# Sheet1.net
KiCad netlist of a schematic drawn in Altium Designer
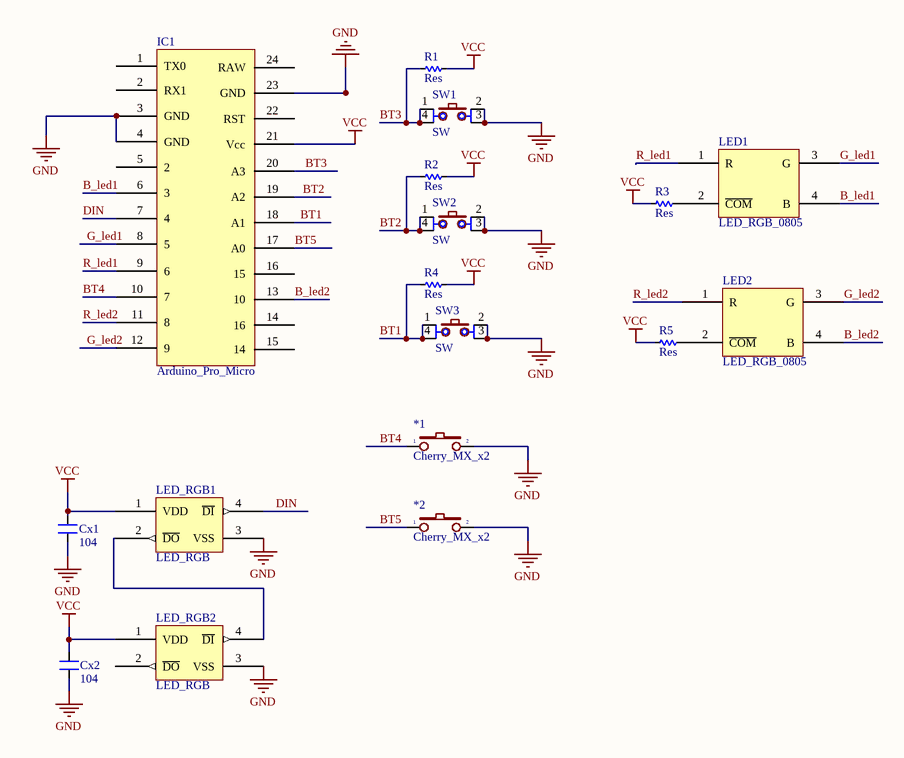
[diagram p0: Sheet1.SchDoc]

(export (version "E")
  (design (tool "Eeschema 10.0.6"))
  (components
    (comp (ref "*1")
      (value "Cherry_MX_x2")
      (footprint "Cherry_Mx_2")
      (libsource (lib "LIBRARY") (part "Cherry_MX_x2"))
    )
    (comp (ref "*2")
      (value "Cherry_MX_x2")
      (footprint "Cherry_Mx_2")
      (libsource (lib "LIBRARY") (part "Cherry_MX_x2"))
    )
    (comp (ref "Cx1") (value "104") (footprint "CN-SMD-0805") (libsource (lib "LIBRARY") (part "CN")))
    (comp (ref "Cx2") (value "104") (footprint "CN-SMD-0805") (libsource (lib "LIBRARY") (part "CN")))
    (comp (ref "IC1")
      (value "Arduino_Pro_Micro")
      (footprint "PCBComponent_1")
      (libsource (lib "LIBRARY") (part "Arduino_Pro_Micro"))
    )
    (comp (ref "LED1")
      (value "LED_RGB_0805")
      (footprint "PCBComponent_1")
      (libsource (lib "LED_RGB_0805") (part "LED_RGB_0805"))
    )
    (comp (ref "LED2")
      (value "LED_RGB_0805")
      (footprint "PCBComponent_1")
      (libsource (lib "LED_RGB_0805") (part "LED_RGB_0805"))
    )
    (comp (ref "LED_RGB1")
      (value "LED_RGB")
      (footprint "PCBComponent_1")
      (description "LED?")
      (libsource (lib "RGB_5050_WS2812B") (part "LED_RGB_5050_WS2812B"))
    )
    (comp (ref "LED_RGB2")
      (value "LED_RGB")
      (footprint "PCBComponent_1")
      (description "LED?")
      (libsource (lib "RGB_5050_WS2812B") (part "LED_RGB_5050_WS2812B"))
    )
    (comp (ref "R1")
      (value "Res")
      (footprint "RES-SMD-0805")
      (description "Resistor")
      (fields
        (field (name "MANUFACTURER") "Generic Components")
        (field (name "PUBLISHER") "Altium Hobart Technology Centre")
      )
      (libsource (lib "LIBRARY") (part "Res-SMD"))
    )
    (comp (ref "R2")
      (value "Res")
      (footprint "RES-SMD-0805")
      (description "Resistor")
      (fields
        (field (name "MANUFACTURER") "Generic Components")
        (field (name "PUBLISHER") "Altium Hobart Technology Centre")
      )
      (libsource (lib "LIBRARY") (part "Res-SMD"))
    )
    (comp (ref "R3")
      (value "Res")
      (footprint "RES-SMD-0805")
      (description "Resistor")
      (fields
        (field (name "MANUFACTURER") "Generic Components")
        (field (name "PUBLISHER") "Altium Hobart Technology Centre")
      )
      (libsource (lib "LIBRARY") (part "Res-SMD"))
    )
    (comp (ref "R4")
      (value "Res")
      (footprint "RES-SMD-0805")
      (description "Resistor")
      (fields
        (field (name "MANUFACTURER") "Generic Components")
        (field (name "PUBLISHER") "Altium Hobart Technology Centre")
      )
      (libsource (lib "LIBRARY") (part "Res-SMD"))
    )
    (comp (ref "R5")
      (value "Res")
      (footprint "RES-SMD-0805")
      (description "Resistor")
      (fields
        (field (name "MANUFACTURER") "Generic Components")
        (field (name "PUBLISHER") "Altium Hobart Technology Centre")
      )
      (libsource (lib "LIBRARY") (part "Res-SMD"))
    )
    (comp (ref "SW1")
      (value "SW")
      (footprint "SW2-DIP")
      (description "Switch button 4 pin")
      (libsource (lib "LIBRARY") (part "SW4"))
    )
    (comp (ref "SW2")
      (value "SW")
      (footprint "SW2-DIP")
      (description "Switch button 4 pin")
      (libsource (lib "LIBRARY") (part "SW4"))
    )
    (comp (ref "SW3")
      (value "SW")
      (footprint "SW2-DIP")
      (description "Switch button 4 pin")
      (libsource (lib "LIBRARY") (part "SW4"))
    )
  )
  (nets
    (net (code "1") (name "/BT1") (class "Default")
      (node (ref "IC1") (pin "18") (pinfunction "A1_18") (pintype "passive"))
      (node (ref "R4") (pin "2") (pinfunction "2_2") (pintype "passive"))
      (node (ref "SW3") (pin "1") (pintype "passive"))
      (node (ref "SW3") (pin "4") (pinfunction "4_4") (pintype "passive"))
    )
    (net (code "2") (name "/BT2") (class "Default")
      (node (ref "IC1") (pin "19") (pinfunction "A2_19") (pintype "passive"))
      (node (ref "R2") (pin "2") (pinfunction "2_2") (pintype "passive"))
      (node (ref "SW2") (pin "1") (pintype "passive"))
      (node (ref "SW2") (pin "4") (pinfunction "4_4") (pintype "passive"))
    )
    (net (code "3") (name "/BT3") (class "Default")
      (node (ref "IC1") (pin "20") (pinfunction "A3_20") (pintype "passive"))
      (node (ref "R1") (pin "2") (pinfunction "2_2") (pintype "passive"))
      (node (ref "SW1") (pin "1") (pintype "passive"))
      (node (ref "SW1") (pin "4") (pinfunction "4_4") (pintype "passive"))
    )
    (net (code "4") (name "/BT4") (class "Default")
      (node (ref "*1") (pin "1") (pinfunction "1_1") (pintype "passive"))
      (node (ref "IC1") (pin "10") (pinfunction "7_10") (pintype "passive"))
    )
    (net (code "5") (name "/BT5") (class "Default")
      (node (ref "*2") (pin "1") (pinfunction "1_1") (pintype "passive"))
      (node (ref "IC1") (pin "17") (pinfunction "A0_17") (pintype "passive"))
    )
    (net (code "6") (name "/B_led1") (class "Default")
      (node (ref "IC1") (pin "6") (pinfunction "3_6") (pintype "passive"))
      (node (ref "LED1") (pin "4") (pinfunction "B_4") (pintype "passive"))
    )
    (net (code "7") (name "/B_led2") (class "Default")
      (node (ref "IC1") (pin "13") (pinfunction "10_13") (pintype "passive"))
      (node (ref "LED2") (pin "4") (pinfunction "B_4") (pintype "passive"))
    )
    (net (code "8") (name "/DIN") (class "Default")
      (node (ref "IC1") (pin "7") (pinfunction "4_7") (pintype "passive"))
      (node (ref "LED_RGB1") (pin "4") (pinfunction "~{DI}_4") (pintype "output"))
    )
    (net (code "9") (name "/G_led1") (class "Default")
      (node (ref "IC1") (pin "8") (pinfunction "5_8") (pintype "passive"))
      (node (ref "LED1") (pin "3") (pinfunction "G_3") (pintype "passive"))
    )
    (net (code "10") (name "/G_led2") (class "Default")
      (node (ref "IC1") (pin "12") (pinfunction "9_12") (pintype "passive"))
      (node (ref "LED2") (pin "3") (pinfunction "G_3") (pintype "passive"))
    )
    (net (code "11") (name "/R_led1") (class "Default")
      (node (ref "IC1") (pin "9") (pinfunction "6_9") (pintype "passive"))
      (node (ref "LED1") (pin "1") (pinfunction "R_1") (pintype "passive"))
    )
    (net (code "12") (name "/R_led2") (class "Default")
      (node (ref "IC1") (pin "11") (pinfunction "8_11") (pintype "passive"))
      (node (ref "LED2") (pin "1") (pinfunction "R_1") (pintype "passive"))
    )
    (net (code "13") (name "GND") (class "Default")
      (node (ref "*1") (pin "2") (pinfunction "2_2") (pintype "passive"))
      (node (ref "*2") (pin "2") (pinfunction "2_2") (pintype "passive"))
      (node (ref "Cx1") (pin "2") (pinfunction "2_2") (pintype "passive"))
      (node (ref "Cx2") (pin "2") (pinfunction "2_2") (pintype "passive"))
      (node (ref "IC1") (pin "23") (pinfunction "GND_23") (pintype "passive"))
      (node (ref "IC1") (pin "3") (pinfunction "GND_3") (pintype "passive"))
      (node (ref "IC1") (pin "4") (pinfunction "GND_4") (pintype "passive"))
      (node (ref "LED_RGB1") (pin "3") (pinfunction "VSS_3") (pintype "passive"))
      (node (ref "LED_RGB2") (pin "3") (pinfunction "VSS_3") (pintype "passive"))
      (node (ref "SW1") (pin "2") (pinfunction "2_2") (pintype "passive"))
      (node (ref "SW1") (pin "3") (pinfunction "3_3") (pintype "passive"))
      (node (ref "SW2") (pin "2") (pinfunction "2_2") (pintype "passive"))
      (node (ref "SW2") (pin "3") (pinfunction "3_3") (pintype "passive"))
      (node (ref "SW3") (pin "2") (pinfunction "2_2") (pintype "passive"))
      (node (ref "SW3") (pin "3") (pinfunction "3_3") (pintype "passive"))
    )
    (net (code "14") (name "Net-(LED1-~{COM})") (class "Default")
      (node (ref "LED1") (pin "2") (pinfunction "~{COM}_2") (pintype "passive"))
      (node (ref "R3") (pin "1") (pinfunction "1_1") (pintype "passive"))
    )
    (net (code "15") (name "Net-(LED2-~{COM})") (class "Default")
      (node (ref "LED2") (pin "2") (pinfunction "~{COM}_2") (pintype "passive"))
      (node (ref "R5") (pin "1") (pinfunction "1_1") (pintype "passive"))
    )
    (net (code "16") (name "Net-(LED_RGB1-~{DO})") (class "Default")
      (node (ref "LED_RGB1") (pin "2") (pinfunction "~{DO}_2") (pintype "output"))
      (node (ref "LED_RGB2") (pin "4") (pinfunction "~{DI}_4") (pintype "output"))
    )
    (net (code "17") (name "VCC") (class "Default")
      (node (ref "Cx1") (pin "1") (pinfunction "1_1") (pintype "passive"))
      (node (ref "Cx2") (pin "1") (pinfunction "1_1") (pintype "passive"))
      (node (ref "IC1") (pin "21") (pinfunction "Vcc_21") (pintype "passive"))
      (node (ref "LED_RGB1") (pin "1") (pinfunction "VDD_1") (pintype "power_in"))
      (node (ref "LED_RGB2") (pin "1") (pinfunction "VDD_1") (pintype "power_in"))
      (node (ref "R1") (pin "1") (pinfunction "1_1") (pintype "passive"))
      (node (ref "R2") (pin "1") (pinfunction "1_1") (pintype "passive"))
      (node (ref "R3") (pin "2") (pinfunction "2_2") (pintype "passive"))
      (node (ref "R4") (pin "1") (pinfunction "1_1") (pintype "passive"))
      (node (ref "R5") (pin "2") (pinfunction "2_2") (pintype "passive"))
    )
    (net (code "18") (name "unconnected-(IC1-2-Pad5)") (class "Default")
      (node (ref "IC1") (pin "5") (pinfunction "2_5") (pintype "passive"))
    )
    (net (code "19") (name "unconnected-(IC1-14-Pad15)") (class "Default")
      (node (ref "IC1") (pin "15") (pinfunction "14_15") (pintype "passive"))
    )
    (net (code "20") (name "unconnected-(IC1-15-Pad16)") (class "Default")
      (node (ref "IC1") (pin "16") (pinfunction "15_16") (pintype "passive"))
    )
    (net (code "21") (name "unconnected-(IC1-16-Pad14)") (class "Default")
      (node (ref "IC1") (pin "14") (pinfunction "16_14") (pintype "passive"))
    )
    (net (code "22") (name "unconnected-(IC1-RAW-Pad24)") (class "Default")
      (node (ref "IC1") (pin "24") (pinfunction "RAW_24") (pintype "passive"))
    )
    (net (code "23") (name "unconnected-(IC1-RST-Pad22)") (class "Default")
      (node (ref "IC1") (pin "22") (pinfunction "RST_22") (pintype "passive"))
    )
    (net (code "24") (name "unconnected-(IC1-RX1-Pad2)") (class "Default")
      (node (ref "IC1") (pin "2") (pinfunction "RX1_2") (pintype "passive"))
    )
    (net (code "25") (name "unconnected-(IC1-TX0-Pad1)") (class "Default")
      (node (ref "IC1") (pin "1") (pinfunction "TX0_1") (pintype "passive"))
    )
    (net (code "26") (name "unconnected-(LED_RGB2-~{DO}-Pad2)") (class "Default")
      (node (ref "LED_RGB2") (pin "2") (pinfunction "~{DO}_2") (pintype "output"))
    )
  )
)
